# LNA_LNANXPSOT1209_v1.net
KiCad netlist of a schematic drawn in Altium Designer
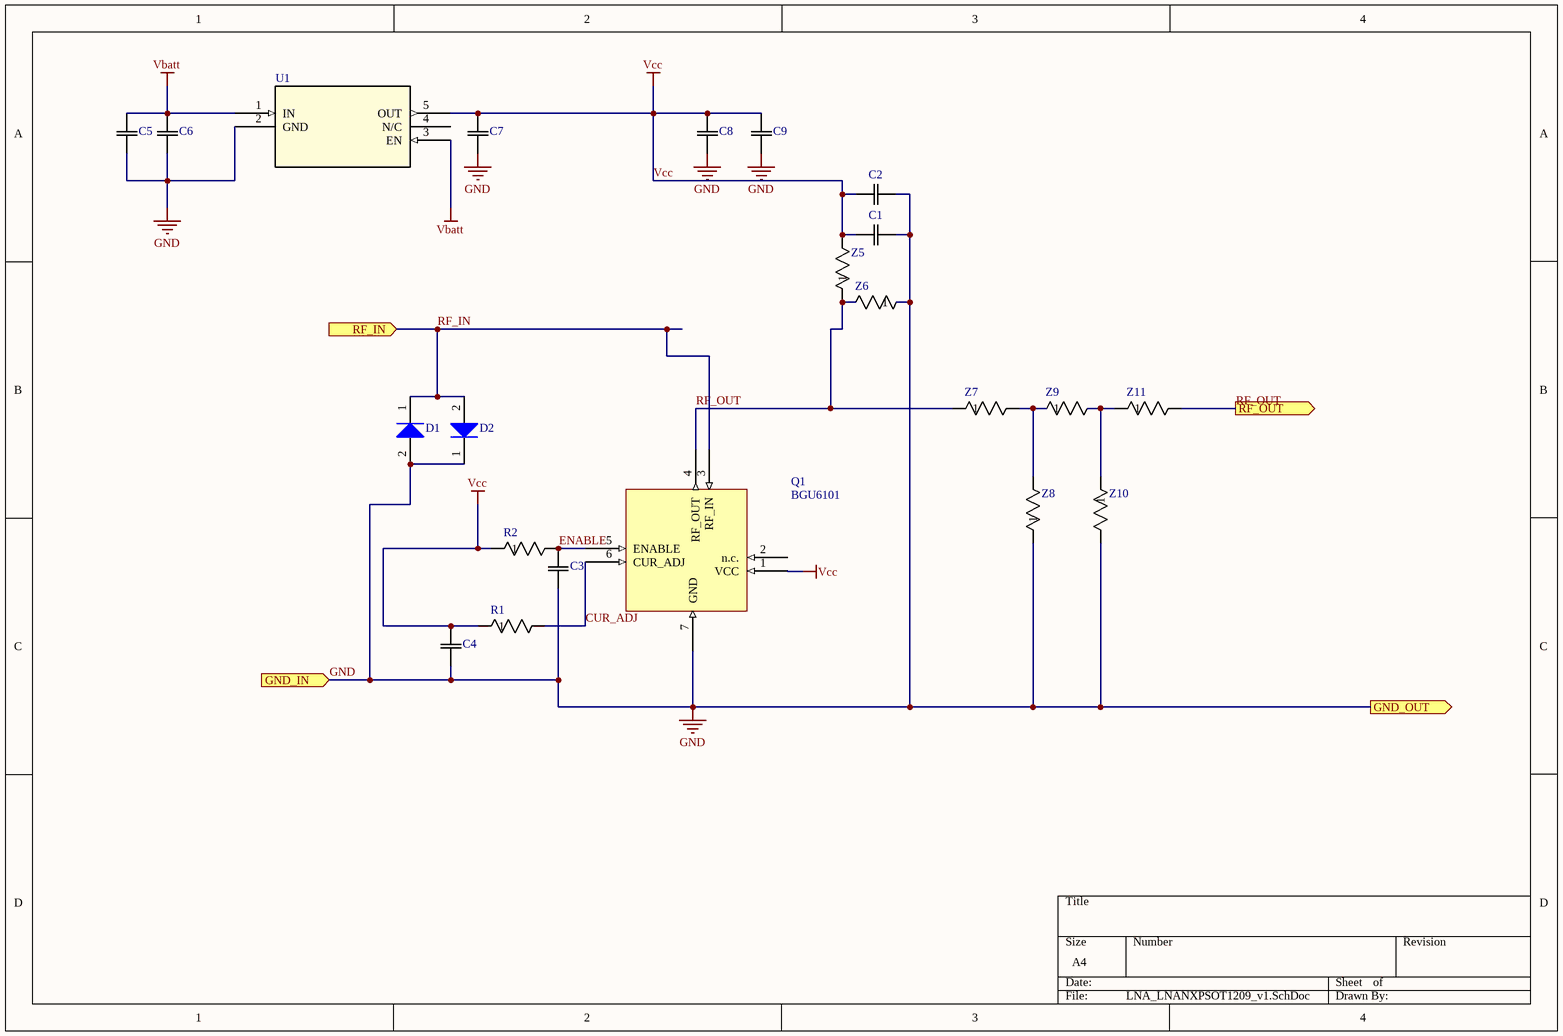
[diagram p0: LNA_LNANXPSOT1209_v1.SchDoc]

(export (version "E")
  (design (tool "Eeschema 10.0.6"))
  (components
    (comp (ref "C1")
      (value "~")
      (footprint "C0201")
      (description "No Description Available")
      (fields
        (field (name "MANUFACTURER_PART_NUMBER") "C0201C270J3GACTU")
        (field (name "COPYRIGHT") "Copyright (C) 2018 Accelerated Designs. All rights reserved")
      )
      (libsource (lib "0201Capacitor_Yageo") (part "C0201C270J3GACTU"))
    )
    (comp (ref "C2")
      (value "~")
      (footprint "C0201")
      (description "No Description Available")
      (fields
        (field (name "MANUFACTURER_PART_NUMBER") "C0201C270J3GACTU")
        (field (name "COPYRIGHT") "Copyright (C) 2018 Accelerated Designs. All rights reserved")
      )
      (libsource (lib "0201Capacitor_Yageo") (part "C0201C270J3GACTU"))
    )
    (comp (ref "C3")
      (value "~")
      (footprint "C0201")
      (description "No Description Available")
      (fields
        (field (name "MANUFACTURER_PART_NUMBER") "C0201C270J3GACTU")
        (field (name "COPYRIGHT") "Copyright (C) 2018 Accelerated Designs. All rights reserved")
      )
      (libsource (lib "0201Capacitor_Yageo") (part "C0201C270J3GACTU"))
    )
    (comp (ref "C4")
      (value "~")
      (footprint "0201Capacitor_Yageo:C0201")
      (description "No Description Available")
      (fields
        (field (name "MANUFACTURER_PART_NUMBER") "C0201C270J3GACTU")
        (field (name "COPYRIGHT") "Copyright (C) 2018 Accelerated Designs. All rights reserved")
      )
      (libsource (lib "0201Capacitor_Yageo") (part "C0201C270J3GACTU"))
    )
    (comp (ref "C5")
      (value "~")
      (footprint "0402Capacitor_Yageo:YAG_CC0402")
      (description "No Description Available")
      (fields
        (field (name "MANUFACTURER_PART_NUMBER") "C0201C270J3GACTU")
        (field (name "COPYRIGHT") "Copyright (C) 2018 Accelerated Designs. All rights reserved")
      )
      (libsource (lib "0201Capacitor_Yageo") (part "C0201C270J3GACTU"))
    )
    (comp (ref "C6")
      (value "~")
      (footprint "0402Capacitor_Yageo:YAG_CC0402")
      (description "No Description Available")
      (fields
        (field (name "MANUFACTURER_PART_NUMBER") "C0201C270J3GACTU")
        (field (name "COPYRIGHT") "Copyright (C) 2018 Accelerated Designs. All rights reserved")
      )
      (libsource (lib "0201Capacitor_Yageo") (part "C0201C270J3GACTU"))
    )
    (comp (ref "C7")
      (value "~")
      (footprint "0402Capacitor_Yageo:YAG_CC0402")
      (description "No Description Available")
      (fields
        (field (name "MANUFACTURER_PART_NUMBER") "C0201C270J3GACTU")
        (field (name "COPYRIGHT") "Copyright (C) 2018 Accelerated Designs. All rights reserved")
      )
      (libsource (lib "0201Capacitor_Yageo") (part "C0201C270J3GACTU"))
    )
    (comp (ref "C8")
      (value "~")
      (footprint "0201Capacitor_Yageo:C0201")
      (description "No Description Available")
      (fields
        (field (name "MANUFACTURER_PART_NUMBER") "C0201C270J3GACTU")
        (field (name "COPYRIGHT") "Copyright (C) 2018 Accelerated Designs. All rights reserved")
      )
      (libsource (lib "0201Capacitor_Yageo") (part "C0201C270J3GACTU"))
    )
    (comp (ref "C9")
      (value "~")
      (footprint "0201Capacitor_Yageo:C0201")
      (description "No Description Available")
      (fields
        (field (name "MANUFACTURER_PART_NUMBER") "C0201C270J3GACTU")
        (field (name "COPYRIGHT") "Copyright (C) 2018 Accelerated Designs. All rights reserved")
      )
      (libsource (lib "0201Capacitor_Yageo") (part "C0201C270J3GACTU"))
    )
    (comp (ref "D1")
      (value "~")
      (footprint "INF-SOD323_V:INF-SOD323_V")
      (description "Single Silicon Schottky Diode, 110 mA IF Max, SOD32, Green")
      (fields (field (name "MANUFACTURER") "Infineon") (field (name "PARTNUMBER") "BAT15-03W"))
      (libsource (lib "Infineon_RFSchottkyDiode_SOD323") (part "BAT15-03W"))
    )
    (comp (ref "D2")
      (value "~")
      (footprint "INF-SOD323_V:INF-SOD323_V")
      (description "Single Silicon Schottky Diode, 110 mA IF Max, SOD32, Green")
      (fields (field (name "MANUFACTURER") "Infineon") (field (name "PARTNUMBER") "BAT15-03W"))
      (libsource (lib "Infineon_RFSchottkyDiode_SOD323") (part "BAT15-03W"))
    )
    (comp (ref "Q1")
      (value "BGU6101")
      (footprint "*PSON50P130X200X35-7N")
      (libsource (lib "Schlib1") (part "BGU6101"))
    )
    (comp (ref "R1")
      (value "~")
      (footprint "RES_RC0201_P6XP3")
      (description "No Description Available")
      (fields
        (field (name "MANUFACTURER_PART_NUMBER") "RC0201FR-0718KL")
        (field (name "COPYRIGHT") "Copyright (C) 2018 Accelerated Designs. All rights reserved")
      )
      (libsource (lib "0201Resistor_Yageo") (part "RC0201FR-0718KL"))
    )
    (comp (ref "R2")
      (value "~")
      (footprint "RES_RC0201_P6XP3")
      (description "No Description Available")
      (fields
        (field (name "MANUFACTURER_PART_NUMBER") "RC0201FR-0718KL")
        (field (name "COPYRIGHT") "Copyright (C) 2018 Accelerated Designs. All rights reserved")
      )
      (libsource (lib "0201Resistor_Yageo") (part "RC0201FR-0718KL"))
    )
    (comp (ref "U1")
      (value "~")
      (footprint "TI_LDO_3V3_SOT325:DBV5")
      (description "No Description Available")
      (fields
        (field (name "MANUFACTURER_PART_NUMBER") "LP5907MFX-3.3/NOPB")
        (field (name "COPYRIGHT") "Copyright (C) 2018 Accelerated Designs. All rights reserved")
      )
      (libsource (lib "TI_LDO_3V3_SOT325") (part "LP5907MFX-3.3/NO"))
    )
    (comp (ref "Z5")
      (value "~")
      (footprint "RES_RC0201_P6XP3")
      (description "No Description Available")
      (fields
        (field (name "MANUFACTURER_PART_NUMBER") "RC0201FR-0718KL")
        (field (name "COPYRIGHT") "Copyright (C) 2018 Accelerated Designs. All rights reserved")
      )
      (libsource (lib "0201Resistor_Yageo") (part "RC0201FR-0718KL"))
    )
    (comp (ref "Z6")
      (value "~")
      (footprint "RES_RC0201_P6XP3")
      (description "No Description Available")
      (fields
        (field (name "MANUFACTURER_PART_NUMBER") "RC0201FR-0718KL")
        (field (name "COPYRIGHT") "Copyright (C) 2018 Accelerated Designs. All rights reserved")
      )
      (libsource (lib "0201Resistor_Yageo") (part "RC0201FR-0718KL"))
    )
    (comp (ref "Z7")
      (value "~")
      (footprint "RES_RC0201_P6XP3")
      (description "No Description Available")
      (fields
        (field (name "MANUFACTURER_PART_NUMBER") "RC0201FR-0718KL")
        (field (name "COPYRIGHT") "Copyright (C) 2018 Accelerated Designs. All rights reserved")
      )
      (libsource (lib "0201Resistor_Yageo") (part "RC0201FR-0718KL"))
    )
    (comp (ref "Z8")
      (value "~")
      (footprint "RES_RC0201_P6XP3")
      (description "No Description Available")
      (fields
        (field (name "MANUFACTURER_PART_NUMBER") "RC0201FR-0718KL")
        (field (name "COPYRIGHT") "Copyright (C) 2018 Accelerated Designs. All rights reserved")
      )
      (libsource (lib "0201Resistor_Yageo") (part "RC0201FR-0718KL"))
    )
    (comp (ref "Z9")
      (value "~")
      (footprint "RES_RC0201_P6XP3")
      (description "No Description Available")
      (fields
        (field (name "MANUFACTURER_PART_NUMBER") "RC0201FR-0718KL")
        (field (name "COPYRIGHT") "Copyright (C) 2018 Accelerated Designs. All rights reserved")
      )
      (libsource (lib "0201Resistor_Yageo") (part "RC0201FR-0718KL"))
    )
    (comp (ref "Z10")
      (value "~")
      (footprint "RES_RC0201_P6XP3")
      (description "No Description Available")
      (fields
        (field (name "MANUFACTURER_PART_NUMBER") "RC0201FR-0718KL")
        (field (name "COPYRIGHT") "Copyright (C) 2018 Accelerated Designs. All rights reserved")
      )
      (libsource (lib "0201Resistor_Yageo") (part "RC0201FR-0718KL"))
    )
    (comp (ref "Z11")
      (value "~")
      (footprint "RES_RC0201_P6XP3")
      (description "No Description Available")
      (fields
        (field (name "MANUFACTURER_PART_NUMBER") "RC0201FR-0718KL")
        (field (name "COPYRIGHT") "Copyright (C) 2018 Accelerated Designs. All rights reserved")
      )
      (libsource (lib "0201Resistor_Yageo") (part "RC0201FR-0718KL"))
    )
  )
  (nets
    (net (code "1") (name "/CUR_ADJ") (class "Default")
      (node (ref "Q1") (pin "6") (pinfunction "CUR_ADJ_6") (pintype "input"))
      (node (ref "R1") (pin "2") (pinfunction "2_2") (pintype "passive"))
    )
    (net (code "2") (name "/ENABLE") (class "Default")
      (node (ref "C3") (pin "2") (pinfunction "2_2") (pintype "passive"))
      (node (ref "Q1") (pin "5") (pinfunction "ENABLE_5") (pintype "input"))
      (node (ref "R2") (pin "2") (pinfunction "2_2") (pintype "passive"))
    )
    (net (code "3") (name "/RF_IN") (class "Default")
      (node (ref "D1") (pin "1") (pinfunction "K_1") (pintype "passive"))
      (node (ref "D2") (pin "2") (pinfunction "A_2") (pintype "passive"))
      (node (ref "Q1") (pin "3") (pinfunction "RF_IN_3") (pintype "input"))
    )
    (net (code "4") (name "/RF_OUT") (class "Default")
      (node (ref "Q1") (pin "4") (pinfunction "RF_OUT_4") (pintype "output"))
      (node (ref "Z11") (pin "2") (pinfunction "2_2") (pintype "passive"))
      (node (ref "Z5") (pin "1") (pinfunction "1_1") (pintype "passive"))
      (node (ref "Z6") (pin "2") (pinfunction "2_2") (pintype "passive"))
      (node (ref "Z7") (pin "1") (pinfunction "1_1") (pintype "passive"))
    )
    (net (code "5") (name "GND") (class "Default")
      (node (ref "C1") (pin "2") (pinfunction "2_2") (pintype "passive"))
      (node (ref "C2") (pin "2") (pinfunction "2_2") (pintype "passive"))
      (node (ref "C3") (pin "1") (pinfunction "1_1") (pintype "passive"))
      (node (ref "C4") (pin "2") (pinfunction "2_2") (pintype "passive"))
      (node (ref "C5") (pin "2") (pinfunction "2_2") (pintype "passive"))
      (node (ref "C6") (pin "2") (pinfunction "2_2") (pintype "passive"))
      (node (ref "C7") (pin "2") (pinfunction "2_2") (pintype "passive"))
      (node (ref "C8") (pin "2") (pinfunction "2_2") (pintype "passive"))
      (node (ref "C9") (pin "2") (pinfunction "2_2") (pintype "passive"))
      (node (ref "D1") (pin "2") (pinfunction "A_2") (pintype "passive"))
      (node (ref "D2") (pin "1") (pinfunction "K_1") (pintype "passive"))
      (node (ref "Q1") (pin "7") (pinfunction "GND_7") (pintype "input"))
      (node (ref "U1") (pin "2") (pinfunction "GND_2") (pintype "power_in"))
      (node (ref "Z10") (pin "2") (pinfunction "2_2") (pintype "passive"))
      (node (ref "Z6") (pin "1") (pinfunction "1_1") (pintype "passive"))
      (node (ref "Z8") (pin "1") (pinfunction "1_1") (pintype "passive"))
    )
    (net (code "6") (name "Net-(Z7-Pad2)") (class "Default")
      (node (ref "Z7") (pin "2") (pinfunction "2_2") (pintype "passive"))
      (node (ref "Z8") (pin "2") (pinfunction "2_2") (pintype "passive"))
      (node (ref "Z9") (pin "1") (pinfunction "1_1") (pintype "passive"))
    )
    (net (code "7") (name "Net-(Z10-Pad1)") (class "Default")
      (node (ref "Z10") (pin "1") (pinfunction "1_1") (pintype "passive"))
      (node (ref "Z11") (pin "1") (pinfunction "1_1") (pintype "passive"))
      (node (ref "Z9") (pin "2") (pinfunction "2_2") (pintype "passive"))
    )
    (net (code "8") (name "Vbatt") (class "Default")
      (node (ref "C5") (pin "1") (pinfunction "1_1") (pintype "passive"))
      (node (ref "C6") (pin "1") (pinfunction "1_1") (pintype "passive"))
      (node (ref "U1") (pin "1") (pinfunction "IN_1") (pintype "input"))
      (node (ref "U1") (pin "3") (pinfunction "EN_3") (pintype "input"))
    )
    (net (code "9") (name "Vcc") (class "Default")
      (node (ref "C1") (pin "1") (pinfunction "1_1") (pintype "passive"))
      (node (ref "C2") (pin "1") (pinfunction "1_1") (pintype "passive"))
      (node (ref "C4") (pin "1") (pinfunction "1_1") (pintype "passive"))
      (node (ref "C7") (pin "1") (pinfunction "1_1") (pintype "passive"))
      (node (ref "C8") (pin "1") (pinfunction "1_1") (pintype "passive"))
      (node (ref "C9") (pin "1") (pinfunction "1_1") (pintype "passive"))
      (node (ref "Q1") (pin "1") (pinfunction "VCC_1") (pintype "input"))
      (node (ref "R1") (pin "1") (pinfunction "1_1") (pintype "passive"))
      (node (ref "R2") (pin "1") (pinfunction "1_1") (pintype "passive"))
      (node (ref "U1") (pin "5") (pinfunction "OUT_5") (pintype "output"))
      (node (ref "Z5") (pin "2") (pinfunction "2_2") (pintype "passive"))
    )
    (net (code "10") (name "unconnected-(Q1-n.c.-Pad2)") (class "Default")
      (node (ref "Q1") (pin "2") (pinfunction "n.c._2") (pintype "input"))
    )
    (net (code "11") (name "unconnected-(U1-N{slash}C-Pad4)") (class "Default")
      (node (ref "U1") (pin "4") (pinfunction "N/C_4") (pintype "passive"))
    )
  )
)
